# Main_Board.net
KiCad netlist of a schematic drawn in EAGLE
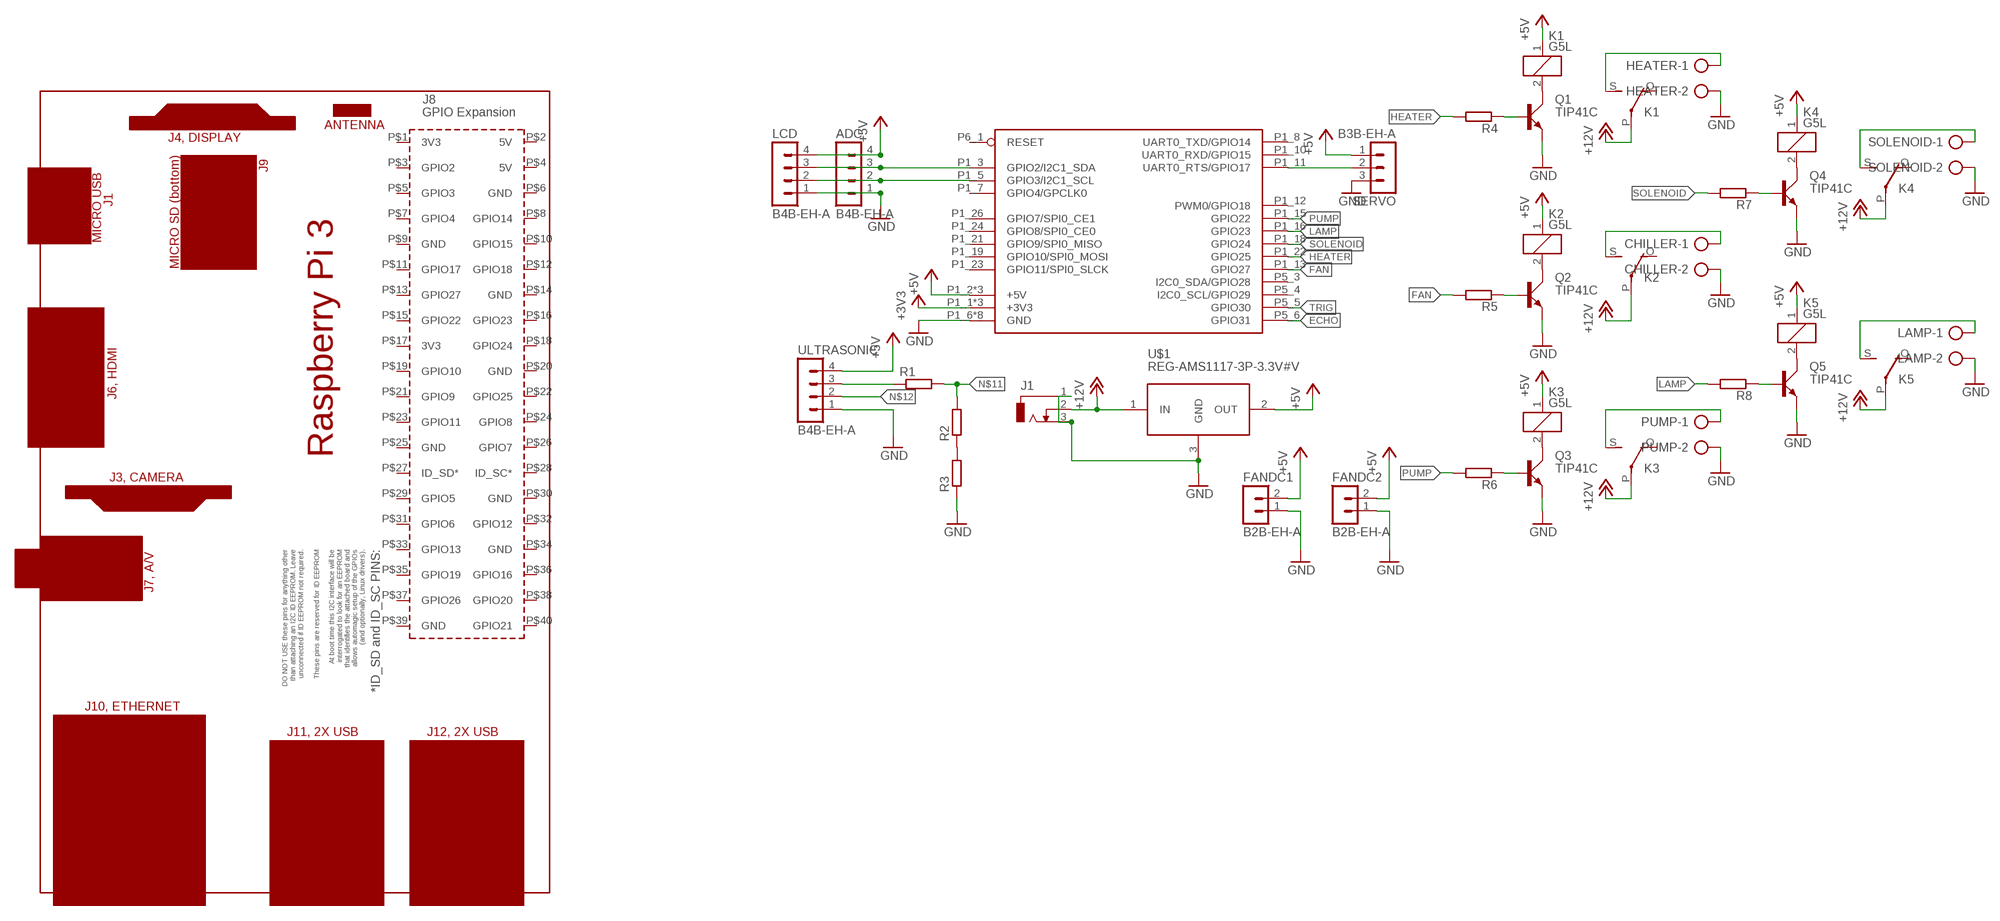
[diagram p0: schematic, sheet 1]

(export (version "E")
  (design (tool "Eeschema 10.0.6"))
  (components
    (comp (ref "ADC")
      (value "B4B-EH-A")
      (footprint "eagle-import:B4B-EH-A")
      (libsource (lib "eagle-import") (part "B4B-EH-A"))
    )
    (comp (ref "CHILLER")
      (value "AK500/2-H")
      (footprint "eagle-import:AK500_2-H")
      (libsource (lib "eagle-import") (part "AK500/2-H"))
    )
    (comp (ref "FANDC1")
      (value "B2B-EH-A")
      (footprint "eagle-import:B2B-EH-A")
      (libsource (lib "eagle-import") (part "B2B-EH-A"))
    )
    (comp (ref "FANDC2")
      (value "B2B-EH-A")
      (footprint "eagle-import:B2B-EH-A")
      (libsource (lib "eagle-import") (part "B2B-EH-A"))
    )
    (comp (ref "HEATER")
      (value "AK500/2-H")
      (footprint "eagle-import:AK500_2-H")
      (libsource (lib "eagle-import") (part "AK500/2-H"))
    )
    (comp (ref "J1")
      (value "DCJ0303")
      (footprint "eagle-import:DCJ0303")
      (libsource (lib "eagle-import") (part "DCJ0303"))
    )
    (comp (ref "K1")
      (value "G5L")
      (footprint "eagle-import:G5LE")
      (libsource (lib "eagle-import") (part "G5L"))
    )
    (comp (ref "K2")
      (value "G5L")
      (footprint "eagle-import:G5LE")
      (libsource (lib "eagle-import") (part "G5L"))
    )
    (comp (ref "K3")
      (value "G5L")
      (footprint "eagle-import:G5LE")
      (libsource (lib "eagle-import") (part "G5L"))
    )
    (comp (ref "K4")
      (value "G5L")
      (footprint "eagle-import:G5LE")
      (libsource (lib "eagle-import") (part "G5L"))
    )
    (comp (ref "K5")
      (value "G5L")
      (footprint "eagle-import:G5LE")
      (libsource (lib "eagle-import") (part "G5L"))
    )
    (comp (ref "LAMP")
      (value "AK500/2-H")
      (footprint "eagle-import:AK500_2-H")
      (libsource (lib "eagle-import") (part "AK500/2-H"))
    )
    (comp (ref "LCD")
      (value "B4B-EH-A")
      (footprint "eagle-import:B4B-EH-A")
      (libsource (lib "eagle-import") (part "B4B-EH-A"))
    )
    (comp (ref "PCB1")
      (value "RPI3")
      (footprint "eagle-import:RPI3")
      (libsource (lib "eagle-import") (part "RPI3"))
    )
    (comp (ref "PUMP")
      (value "AK500/2-H")
      (footprint "eagle-import:AK500_2-H")
      (libsource (lib "eagle-import") (part "AK500/2-H"))
    )
    (comp (ref "Q1")
      (value "TIP41C")
      (footprint "eagle-import:TO220AV")
      (libsource (lib "eagle-import") (part "TIP41C"))
    )
    (comp (ref "Q2")
      (value "TIP41C")
      (footprint "eagle-import:TO220AV")
      (libsource (lib "eagle-import") (part "TIP41C"))
    )
    (comp (ref "Q3")
      (value "TIP41C")
      (footprint "eagle-import:TO220AV")
      (libsource (lib "eagle-import") (part "TIP41C"))
    )
    (comp (ref "Q4")
      (value "TIP41C")
      (footprint "eagle-import:TO220AV")
      (libsource (lib "eagle-import") (part "TIP41C"))
    )
    (comp (ref "Q5")
      (value "TIP41C")
      (footprint "eagle-import:TO220AV")
      (libsource (lib "eagle-import") (part "TIP41C"))
    )
    (comp (ref "R1")
      (value "R-EU_0207/15")
      (footprint "eagle-import:0207_15")
      (libsource (lib "eagle-import") (part "R-EU_0207/15"))
    )
    (comp (ref "R2")
      (value "R-EU_0207/15")
      (footprint "eagle-import:0207_15")
      (libsource (lib "eagle-import") (part "R-EU_0207/15"))
    )
    (comp (ref "R3")
      (value "R-EU_0207/15")
      (footprint "eagle-import:0207_15")
      (libsource (lib "eagle-import") (part "R-EU_0207/15"))
    )
    (comp (ref "R4")
      (value "R-EU_0207/15")
      (footprint "eagle-import:0207_15")
      (libsource (lib "eagle-import") (part "R-EU_0207/15"))
    )
    (comp (ref "R5")
      (value "R-EU_0207/15")
      (footprint "eagle-import:0207_15")
      (libsource (lib "eagle-import") (part "R-EU_0207/15"))
    )
    (comp (ref "R6")
      (value "R-EU_0207/15")
      (footprint "eagle-import:0207_15")
      (libsource (lib "eagle-import") (part "R-EU_0207/15"))
    )
    (comp (ref "R7")
      (value "R-EU_0207/15")
      (footprint "eagle-import:0207_15")
      (libsource (lib "eagle-import") (part "R-EU_0207/15"))
    )
    (comp (ref "R8")
      (value "R-EU_0207/15")
      (footprint "eagle-import:0207_15")
      (libsource (lib "eagle-import") (part "R-EU_0207/15"))
    )
    (comp (ref "SERVO")
      (value "B3B-EH-A")
      (footprint "eagle-import:B3B-EH-A")
      (libsource (lib "eagle-import") (part "B3B-EH-A"))
    )
    (comp (ref "SOLENOID")
      (value "AK500/2-H")
      (footprint "eagle-import:AK500_2-H")
      (libsource (lib "eagle-import") (part "AK500/2-H"))
    )
    (comp (ref "U$1")
      (value "REG-AMS1117-3P-3.3V#V")
      (footprint "eagle-import:REG-AMS1117-3P#V")
      (libsource (lib "eagle-import") (part "REG-AMS1117-3P-#V3.3V"))
    )
    (comp (ref "U$3")
      (value "RPI-B-V2NO_SHIELD")
      (footprint "eagle-import:RPI-B-V2")
      (libsource (lib "eagle-import") (part "RPI-B-V2NO_SHIELD"))
    )
    (comp (ref "ULTRASONIC")
      (value "B4B-EH-A")
      (footprint "eagle-import:B4B-EH-A")
      (libsource (lib "eagle-import") (part "B4B-EH-A"))
    )
  )
  (nets
    (net (code "1") (name "+3V3") (class "Default")
      (node (ref "U$3") (pin "P1_1") (pinfunction "+3V3_P1_1") (pintype "power_in"))
      (node (ref "U$3") (pin "P1_17") (pinfunction "+3V3_P1_17") (pintype "power_in"))
      (node (ref "U$3") (pin "P5_2") (pinfunction "+3V3_P5_2") (pintype "power_in"))
    )
    (net (code "2") (name "+5V") (class "Default")
      (node (ref "ADC") (pin "4") (pinfunction "4_4") (pintype "passive"))
      (node (ref "FANDC1") (pin "2") (pinfunction "2_2") (pintype "passive"))
      (node (ref "FANDC2") (pin "2") (pinfunction "2_2") (pintype "passive"))
      (node (ref "K1") (pin "1") (pinfunction "1_1") (pintype "passive"))
      (node (ref "K2") (pin "1") (pinfunction "1_1") (pintype "passive"))
      (node (ref "K3") (pin "1") (pinfunction "1_1") (pintype "passive"))
      (node (ref "K4") (pin "1") (pinfunction "1_1") (pintype "passive"))
      (node (ref "K5") (pin "1") (pinfunction "1_1") (pintype "passive"))
      (node (ref "LCD") (pin "4") (pinfunction "4_4") (pintype "passive"))
      (node (ref "SERVO") (pin "1") (pinfunction "1_1") (pintype "passive"))
      (node (ref "U$1") (pin "2") (pinfunction "OUT_2") (pintype "bidirectional"))
      (node (ref "U$3") (pin "P1_2") (pinfunction "+5V_P1_2") (pintype "power_in"))
      (node (ref "U$3") (pin "P1_4") (pinfunction "+5V_P1_4") (pintype "power_in"))
      (node (ref "U$3") (pin "P5_1") (pinfunction "+5V_P5_1") (pintype "power_in"))
      (node (ref "ULTRASONIC") (pin "4") (pinfunction "4_4") (pintype "passive"))
    )
    (net (code "3") (name "+12V") (class "Default")
      (node (ref "J1") (pin "2") (pinfunction "2_2") (pintype "passive"))
      (node (ref "K1") (pin "P") (pinfunction "P_P") (pintype "passive"))
      (node (ref "K2") (pin "P") (pinfunction "P_P") (pintype "passive"))
      (node (ref "K3") (pin "P") (pinfunction "P_P") (pintype "passive"))
      (node (ref "K4") (pin "P") (pinfunction "P_P") (pintype "passive"))
      (node (ref "K5") (pin "P") (pinfunction "P_P") (pintype "passive"))
      (node (ref "U$1") (pin "1") (pinfunction "IN_1") (pintype "bidirectional"))
    )
    (net (code "4") (name "/I2C0_SCL{slash}GPIO29") (class "Default")
      (node (ref "U$3") (pin "P5_4") (pinfunction "I2C0_SCL/GPIO29_P5_4") (pintype "power_in"))
    )
    (net (code "5") (name "/I2C0_SDA{slash}GPIO28") (class "Default")
      (node (ref "U$3") (pin "P5_3") (pinfunction "I2C0_SDA/GPIO28_P5_3") (pintype "power_in"))
    )
    (net (code "6") (name "/RESET") (class "Default")
      (node (ref "U$3") (pin "P6_1") (pinfunction "RESET_P6_1") (pintype "power_in"))
    )
    (net (code "7") (name "ECHO") (class "Default")
      (node (ref "U$3") (pin "P5_6") (pinfunction "GPIO31_P5_6") (pintype "power_in"))
    )
    (net (code "8") (name "FAN") (class "Default")
      (node (ref "R5") (pin "2") (pinfunction "2_2") (pintype "passive"))
      (node (ref "U$3") (pin "P1_13") (pinfunction "GPIO27_P1_13") (pintype "bidirectional"))
    )
    (net (code "9") (name "GND") (class "Default")
      (node (ref "ADC") (pin "1") (pinfunction "1_1") (pintype "passive"))
      (node (ref "CHILLER") (pin "2") (pinfunction "KL_2") (pintype "passive"))
      (node (ref "FANDC1") (pin "1") (pinfunction "1_1") (pintype "passive"))
      (node (ref "FANDC2") (pin "1") (pinfunction "1_1") (pintype "passive"))
      (node (ref "HEATER") (pin "2") (pinfunction "KL_2") (pintype "passive"))
      (node (ref "J1") (pin "1") (pinfunction "1_1") (pintype "passive"))
      (node (ref "J1") (pin "3") (pinfunction "3_3") (pintype "passive"))
      (node (ref "LAMP") (pin "2") (pinfunction "KL_2") (pintype "passive"))
      (node (ref "LCD") (pin "1") (pinfunction "1_1") (pintype "passive"))
      (node (ref "PUMP") (pin "2") (pinfunction "KL_2") (pintype "passive"))
      (node (ref "Q1") (pin "E") (pinfunction "E_E") (pintype "passive"))
      (node (ref "Q2") (pin "E") (pinfunction "E_E") (pintype "passive"))
      (node (ref "Q3") (pin "E") (pinfunction "E_E") (pintype "passive"))
      (node (ref "Q4") (pin "E") (pinfunction "E_E") (pintype "passive"))
      (node (ref "Q5") (pin "E") (pinfunction "E_E") (pintype "passive"))
      (node (ref "R3") (pin "1") (pinfunction "1_1") (pintype "passive"))
      (node (ref "SERVO") (pin "3") (pinfunction "3_3") (pintype "passive"))
      (node (ref "SOLENOID") (pin "2") (pinfunction "KL_2") (pintype "passive"))
      (node (ref "U$1") (pin "3") (pinfunction "GND_3") (pintype "bidirectional"))
      (node (ref "U$3") (pin "P1_14") (pinfunction "GND_P1_14") (pintype "power_in"))
      (node (ref "U$3") (pin "P1_20") (pinfunction "GND_P1_20") (pintype "power_in"))
      (node (ref "U$3") (pin "P1_25") (pinfunction "GND_P1_25") (pintype "power_in"))
      (node (ref "U$3") (pin "P1_6") (pinfunction "GND_P1_6") (pintype "power_in"))
      (node (ref "U$3") (pin "P1_9") (pinfunction "GND_P1_9") (pintype "power_in"))
      (node (ref "U$3") (pin "P5_7") (pinfunction "GND_P5_7") (pintype "power_in"))
      (node (ref "U$3") (pin "P5_8") (pinfunction "GND_P5_8") (pintype "power_in"))
      (node (ref "U$3") (pin "P6_2") (pinfunction "GND_P6_2") (pintype "power_in"))
      (node (ref "ULTRASONIC") (pin "1") (pinfunction "1_1") (pintype "passive"))
    )
    (net (code "10") (name "HEATER") (class "Default")
      (node (ref "R4") (pin "2") (pinfunction "2_2") (pintype "passive"))
      (node (ref "U$3") (pin "P1_22") (pinfunction "GPIO25_P1_22") (pintype "bidirectional"))
    )
    (net (code "11") (name "LAMP") (class "Default")
      (node (ref "R8") (pin "2") (pinfunction "2_2") (pintype "passive"))
      (node (ref "U$3") (pin "P1_16") (pinfunction "GPIO23_P1_16") (pintype "bidirectional"))
    )
    (net (code "12") (name "N$11") (class "Default")
      (node (ref "R1") (pin "2") (pinfunction "2_2") (pintype "passive"))
      (node (ref "R2") (pin "2") (pinfunction "2_2") (pintype "passive"))
    )
    (net (code "13") (name "N$12") (class "Default")
      (node (ref "ULTRASONIC") (pin "2") (pinfunction "2_2") (pintype "passive"))
    )
    (net (code "14") (name "Net-(CHILLERA-KL)") (class "Default")
      (node (ref "CHILLER") (pin "1") (pinfunction "KL_1") (pintype "passive"))
      (node (ref "K2") (pin "S") (pinfunction "S_S") (pintype "passive"))
    )
    (net (code "15") (name "Net-(HEATERA-KL)") (class "Default")
      (node (ref "HEATER") (pin "1") (pinfunction "KL_1") (pintype "passive"))
      (node (ref "K1") (pin "S") (pinfunction "S_S") (pintype "passive"))
    )
    (net (code "16") (name "Net-(K1-Pad2)") (class "Default")
      (node (ref "K1") (pin "2") (pinfunction "2_2") (pintype "passive"))
      (node (ref "Q1") (pin "C") (pinfunction "C_C") (pintype "passive"))
    )
    (net (code "17") (name "Net-(K2-Pad2)") (class "Default")
      (node (ref "K2") (pin "2") (pinfunction "2_2") (pintype "passive"))
      (node (ref "Q2") (pin "C") (pinfunction "C_C") (pintype "passive"))
    )
    (net (code "18") (name "Net-(K3-Pad2)") (class "Default")
      (node (ref "K3") (pin "2") (pinfunction "2_2") (pintype "passive"))
      (node (ref "Q3") (pin "C") (pinfunction "C_C") (pintype "passive"))
    )
    (net (code "19") (name "Net-(K4-Pad2)") (class "Default")
      (node (ref "K4") (pin "2") (pinfunction "2_2") (pintype "passive"))
      (node (ref "Q4") (pin "C") (pinfunction "C_C") (pintype "passive"))
    )
    (net (code "20") (name "Net-(K5-Pad2)") (class "Default")
      (node (ref "K5") (pin "2") (pinfunction "2_2") (pintype "passive"))
      (node (ref "Q5") (pin "C") (pinfunction "C_C") (pintype "passive"))
    )
    (net (code "21") (name "Net-(LAMPA-KL)") (class "Default")
      (node (ref "K5") (pin "S") (pinfunction "S_S") (pintype "passive"))
      (node (ref "LAMP") (pin "1") (pinfunction "KL_1") (pintype "passive"))
    )
    (net (code "22") (name "Net-(PUMPA-KL)") (class "Default")
      (node (ref "K3") (pin "S") (pinfunction "S_S") (pintype "passive"))
      (node (ref "PUMP") (pin "1") (pinfunction "KL_1") (pintype "passive"))
    )
    (net (code "23") (name "Net-(Q1-PadB)") (class "Default")
      (node (ref "Q1") (pin "B") (pinfunction "B_B") (pintype "passive"))
      (node (ref "R4") (pin "1") (pinfunction "1_1") (pintype "passive"))
    )
    (net (code "24") (name "Net-(Q2-PadB)") (class "Default")
      (node (ref "Q2") (pin "B") (pinfunction "B_B") (pintype "passive"))
      (node (ref "R5") (pin "1") (pinfunction "1_1") (pintype "passive"))
    )
    (net (code "25") (name "Net-(Q3-PadB)") (class "Default")
      (node (ref "Q3") (pin "B") (pinfunction "B_B") (pintype "passive"))
      (node (ref "R6") (pin "1") (pinfunction "1_1") (pintype "passive"))
    )
    (net (code "26") (name "Net-(Q4-PadB)") (class "Default")
      (node (ref "Q4") (pin "B") (pinfunction "B_B") (pintype "passive"))
      (node (ref "R7") (pin "1") (pinfunction "1_1") (pintype "passive"))
    )
    (net (code "27") (name "Net-(Q5-PadB)") (class "Default")
      (node (ref "Q5") (pin "B") (pinfunction "B_B") (pintype "passive"))
      (node (ref "R8") (pin "1") (pinfunction "1_1") (pintype "passive"))
    )
    (net (code "28") (name "Net-(R1-Pad1)") (class "Default")
      (node (ref "R1") (pin "1") (pinfunction "1_1") (pintype "passive"))
      (node (ref "ULTRASONIC") (pin "3") (pinfunction "3_3") (pintype "passive"))
    )
    (net (code "29") (name "Net-(R2-Pad1)") (class "Default")
      (node (ref "R2") (pin "1") (pinfunction "1_1") (pintype "passive"))
      (node (ref "R3") (pin "2") (pinfunction "2_2") (pintype "passive"))
    )
    (net (code "30") (name "Net-(SOLENOIDA-KL)") (class "Default")
      (node (ref "K4") (pin "S") (pinfunction "S_S") (pintype "passive"))
      (node (ref "SOLENOID") (pin "1") (pinfunction "KL_1") (pintype "passive"))
    )
    (net (code "31") (name "Net-(U$3-GPIO2{slash}I2C1_SDA)") (class "Default")
      (node (ref "ADC") (pin "3") (pinfunction "3_3") (pintype "passive"))
      (node (ref "LCD") (pin "3") (pinfunction "3_3") (pintype "passive"))
      (node (ref "U$3") (pin "P1_3") (pinfunction "GPIO2/I2C1_SDA_P1_3") (pintype "bidirectional"))
    )
    (net (code "32") (name "Net-(U$3-GPIO3{slash}I2C1_SCL)") (class "Default")
      (node (ref "ADC") (pin "2") (pinfunction "2_2") (pintype "passive"))
      (node (ref "LCD") (pin "2") (pinfunction "2_2") (pintype "passive"))
      (node (ref "U$3") (pin "P1_5") (pinfunction "GPIO3/I2C1_SCL_P1_5") (pintype "bidirectional"))
    )
    (net (code "33") (name "Net-(U$3-UART0_RTS{slash}GPIO17)") (class "Default")
      (node (ref "SERVO") (pin "2") (pinfunction "2_2") (pintype "passive"))
      (node (ref "U$3") (pin "P1_11") (pinfunction "UART0_RTS/GPIO17_P1_11") (pintype "bidirectional"))
    )
    (net (code "34") (name "PUMP") (class "Default")
      (node (ref "R6") (pin "2") (pinfunction "2_2") (pintype "passive"))
      (node (ref "U$3") (pin "P1_15") (pinfunction "GPIO22_P1_15") (pintype "bidirectional"))
    )
    (net (code "35") (name "SOLENOID") (class "Default")
      (node (ref "R7") (pin "2") (pinfunction "2_2") (pintype "passive"))
      (node (ref "U$3") (pin "P1_18") (pinfunction "GPIO24_P1_18") (pintype "bidirectional"))
    )
    (net (code "36") (name "TRIG") (class "Default")
      (node (ref "U$3") (pin "P5_5") (pinfunction "GPIO30_P5_5") (pintype "power_in"))
    )
    (net (code "37") (name "unconnected-(K1-PadO)") (class "Default")
      (node (ref "K1") (pin "O") (pinfunction "O_O") (pintype "passive"))
    )
    (net (code "38") (name "unconnected-(K2-PadO)") (class "Default")
      (node (ref "K2") (pin "O") (pinfunction "O_O") (pintype "passive"))
    )
    (net (code "39") (name "unconnected-(K3-PadO)") (class "Default")
      (node (ref "K3") (pin "O") (pinfunction "O_O") (pintype "passive"))
    )
    (net (code "40") (name "unconnected-(K4-PadO)") (class "Default")
      (node (ref "K4") (pin "O") (pinfunction "O_O") (pintype "passive"))
    )
    (net (code "41") (name "unconnected-(K5-PadO)") (class "Default")
      (node (ref "K5") (pin "O") (pinfunction "O_O") (pintype "passive"))
    )
    (net (code "42") (name "unconnected-(PCB1-3V3-PadP$1)") (class "Default")
      (node (ref "PCB1") (pin "P$1") (pinfunction "3V3_P$1") (pintype "bidirectional"))
    )
    (net (code "43") (name "unconnected-(PCB1-3V3-PadP$17)") (class "Default")
      (node (ref "PCB1") (pin "P$17") (pinfunction "3V3_P$17") (pintype "bidirectional"))
    )
    (net (code "44") (name "unconnected-(PCB1-5V-PadP$2)") (class "Default")
      (node (ref "PCB1") (pin "P$2") (pinfunction "5V_P$2") (pintype "bidirectional"))
    )
    (net (code "45") (name "unconnected-(PCB1-5V-PadP$4)") (class "Default")
      (node (ref "PCB1") (pin "P$4") (pinfunction "5V_P$4") (pintype "bidirectional"))
    )
    (net (code "46") (name "unconnected-(PCB1-GND-PadP$6)") (class "Default")
      (node (ref "PCB1") (pin "P$6") (pinfunction "GND_P$6") (pintype "bidirectional"))
    )
    (net (code "47") (name "unconnected-(PCB1-GND-PadP$9)") (class "Default")
      (node (ref "PCB1") (pin "P$9") (pinfunction "GND_P$9") (pintype "bidirectional"))
    )
    (net (code "48") (name "unconnected-(PCB1-GND-PadP$14)") (class "Default")
      (node (ref "PCB1") (pin "P$14") (pinfunction "GND_P$14") (pintype "bidirectional"))
    )
    (net (code "49") (name "unconnected-(PCB1-GND-PadP$20)") (class "Default")
      (node (ref "PCB1") (pin "P$20") (pinfunction "GND_P$20") (pintype "bidirectional"))
    )
    (net (code "50") (name "unconnected-(PCB1-GND-PadP$25)") (class "Default")
      (node (ref "PCB1") (pin "P$25") (pinfunction "GND_P$25") (pintype "bidirectional"))
    )
    (net (code "51") (name "unconnected-(PCB1-GND-PadP$30)") (class "Default")
      (node (ref "PCB1") (pin "P$30") (pinfunction "GND_P$30") (pintype "bidirectional"))
    )
    (net (code "52") (name "unconnected-(PCB1-GND-PadP$34)") (class "Default")
      (node (ref "PCB1") (pin "P$34") (pinfunction "GND_P$34") (pintype "bidirectional"))
    )
    (net (code "53") (name "unconnected-(PCB1-GND-PadP$39)") (class "Default")
      (node (ref "PCB1") (pin "P$39") (pinfunction "GND_P$39") (pintype "bidirectional"))
    )
    (net (code "54") (name "unconnected-(PCB1-GPIO2-PadP$3)") (class "Default")
      (node (ref "PCB1") (pin "P$3") (pinfunction "GPIO2_P$3") (pintype "bidirectional"))
    )
    (net (code "55") (name "unconnected-(PCB1-GPIO3-PadP$5)") (class "Default")
      (node (ref "PCB1") (pin "P$5") (pinfunction "GPIO3_P$5") (pintype "bidirectional"))
    )
    (net (code "56") (name "unconnected-(PCB1-GPIO4-PadP$7)") (class "Default")
      (node (ref "PCB1") (pin "P$7") (pinfunction "GPIO4_P$7") (pintype "bidirectional"))
    )
    (net (code "57") (name "unconnected-(PCB1-GPIO5-PadP$29)") (class "Default")
      (node (ref "PCB1") (pin "P$29") (pinfunction "GPIO5_P$29") (pintype "bidirectional"))
    )
    (net (code "58") (name "unconnected-(PCB1-GPIO6-PadP$31)") (class "Default")
      (node (ref "PCB1") (pin "P$31") (pinfunction "GPIO6_P$31") (pintype "bidirectional"))
    )
    (net (code "59") (name "unconnected-(PCB1-GPIO7-PadP$26)") (class "Default")
      (node (ref "PCB1") (pin "P$26") (pinfunction "GPIO7_P$26") (pintype "bidirectional"))
    )
    (net (code "60") (name "unconnected-(PCB1-GPIO8-PadP$24)") (class "Default")
      (node (ref "PCB1") (pin "P$24") (pinfunction "GPIO8_P$24") (pintype "bidirectional"))
    )
    (net (code "61") (name "unconnected-(PCB1-GPIO9-PadP$21)") (class "Default")
      (node (ref "PCB1") (pin "P$21") (pinfunction "GPIO9_P$21") (pintype "bidirectional"))
    )
    (net (code "62") (name "unconnected-(PCB1-GPIO10-PadP$19)") (class "Default")
      (node (ref "PCB1") (pin "P$19") (pinfunction "GPIO10_P$19") (pintype "bidirectional"))
    )
    (net (code "63") (name "unconnected-(PCB1-GPIO11-PadP$23)") (class "Default")
      (node (ref "PCB1") (pin "P$23") (pinfunction "GPIO11_P$23") (pintype "bidirectional"))
    )
    (net (code "64") (name "unconnected-(PCB1-GPIO12-PadP$32)") (class "Default")
      (node (ref "PCB1") (pin "P$32") (pinfunction "GPIO12_P$32") (pintype "bidirectional"))
    )
    (net (code "65") (name "unconnected-(PCB1-GPIO13-PadP$33)") (class "Default")
      (node (ref "PCB1") (pin "P$33") (pinfunction "GPIO13_P$33") (pintype "bidirectional"))
    )
    (net (code "66") (name "unconnected-(PCB1-GPIO14-PadP$8)") (class "Default")
      (node (ref "PCB1") (pin "P$8") (pinfunction "GPIO14_P$8") (pintype "bidirectional"))
    )
    (net (code "67") (name "unconnected-(PCB1-GPIO15-PadP$10)") (class "Default")
      (node (ref "PCB1") (pin "P$10") (pinfunction "GPIO15_P$10") (pintype "bidirectional"))
    )
    (net (code "68") (name "unconnected-(PCB1-GPIO16-PadP$36)") (class "Default")
      (node (ref "PCB1") (pin "P$36") (pinfunction "GPIO16_P$36") (pintype "bidirectional"))
    )
    (net (code "69") (name "unconnected-(PCB1-GPIO17-PadP$11)") (class "Default")
      (node (ref "PCB1") (pin "P$11") (pinfunction "GPIO17_P$11") (pintype "bidirectional"))
    )
    (net (code "70") (name "unconnected-(PCB1-GPIO18-PadP$12)") (class "Default")
      (node (ref "PCB1") (pin "P$12") (pinfunction "GPIO18_P$12") (pintype "bidirectional"))
    )
    (net (code "71") (name "unconnected-(PCB1-GPIO19-PadP$35)") (class "Default")
      (node (ref "PCB1") (pin "P$35") (pinfunction "GPIO19_P$35") (pintype "bidirectional"))
    )
    (net (code "72") (name "unconnected-(PCB1-GPIO20-PadP$38)") (class "Default")
      (node (ref "PCB1") (pin "P$38") (pinfunction "GPIO20_P$38") (pintype "bidirectional"))
    )
    (net (code "73") (name "unconnected-(PCB1-GPIO21-PadP$40)") (class "Default")
      (node (ref "PCB1") (pin "P$40") (pinfunction "GPIO21_P$40") (pintype "bidirectional"))
    )
    (net (code "74") (name "unconnected-(PCB1-GPIO22-PadP$15)") (class "Default")
      (node (ref "PCB1") (pin "P$15") (pinfunction "GPIO22_P$15") (pintype "bidirectional"))
    )
    (net (code "75") (name "unconnected-(PCB1-GPIO23-PadP$16)") (class "Default")
      (node (ref "PCB1") (pin "P$16") (pinfunction "GPIO23_P$16") (pintype "bidirectional"))
    )
    (net (code "76") (name "unconnected-(PCB1-GPIO24-PadP$18)") (class "Default")
      (node (ref "PCB1") (pin "P$18") (pinfunction "GPIO24_P$18") (pintype "bidirectional"))
    )
    (net (code "77") (name "unconnected-(PCB1-GPIO25-PadP$22)") (class "Default")
      (node (ref "PCB1") (pin "P$22") (pinfunction "GPIO25_P$22") (pintype "bidirectional"))
    )
    (net (code "78") (name "unconnected-(PCB1-GPIO26-PadP$37)") (class "Default")
      (node (ref "PCB1") (pin "P$37") (pinfunction "GPIO26_P$37") (pintype "bidirectional"))
    )
    (net (code "79") (name "unconnected-(PCB1-GPIO27-PadP$13)") (class "Default")
      (node (ref "PCB1") (pin "P$13") (pinfunction "GPIO27_P$13") (pintype "bidirectional"))
    )
    (net (code "80") (name "unconnected-(PCB1-ID_SC*-PadP$28)") (class "Default")
      (node (ref "PCB1") (pin "P$28") (pinfunction "ID_SC*_P$28") (pintype "bidirectional"))
    )
    (net (code "81") (name "unconnected-(PCB1-ID_SD*-PadP$27)") (class "Default")
      (node (ref "PCB1") (pin "P$27") (pinfunction "ID_SD*_P$27") (pintype "bidirectional"))
    )
    (net (code "82") (name "unconnected-(U$3-GPIO4{slash}GPCLK0-PadP1_7)") (class "Default")
      (node (ref "U$3") (pin "P1_7") (pinfunction "GPIO4/GPCLK0_P1_7") (pintype "bidirectional"))
    )
    (net (code "83") (name "unconnected-(U$3-GPIO7{slash}SPI0_CE1-PadP1_26)") (class "Default")
      (node (ref "U$3") (pin "P1_26") (pinfunction "GPIO7/SPI0_CE1_P1_26") (pintype "bidirectional"))
    )
    (net (code "84") (name "unconnected-(U$3-GPIO8{slash}SPI0_CE0-PadP1_24)") (class "Default")
      (node (ref "U$3") (pin "P1_24") (pinfunction "GPIO8/SPI0_CE0_P1_24") (pintype "bidirectional"))
    )
    (net (code "85") (name "unconnected-(U$3-GPIO9{slash}SPI0_MISO-PadP1_21)") (class "Default")
      (node (ref "U$3") (pin "P1_21") (pinfunction "GPIO9/SPI0_MISO_P1_21") (pintype "bidirectional"))
    )
    (net (code "86") (name "unconnected-(U$3-GPIO10{slash}SPI0_MOSI-PadP1_19)") (class "Default")
      (node (ref "U$3") (pin "P1_19") (pinfunction "GPIO10/SPI0_MOSI_P1_19") (pintype "bidirectional"))
    )
    (net (code "87") (name "unconnected-(U$3-GPIO11{slash}SPI0_SLCK-PadP1_23)") (class "Default")
      (node (ref "U$3") (pin "P1_23") (pinfunction "GPIO11/SPI0_SLCK_P1_23") (pintype "bidirectional"))
    )
    (net (code "88") (name "unconnected-(U$3-PWM0{slash}GPIO18-PadP1_12)") (class "Default")
      (node (ref "U$3") (pin "P1_12") (pinfunction "PWM0/GPIO18_P1_12") (pintype "bidirectional"))
    )
    (net (code "89") (name "unconnected-(U$3-UART0_RXD{slash}GPIO15-PadP1_10)") (class "Default")
      (node (ref "U$3") (pin "P1_10") (pinfunction "UART0_RXD/GPIO15_P1_10") (pintype "bidirectional"))
    )
    (net (code "90") (name "unconnected-(U$3-UART0_TXD{slash}GPIO14-PadP1_8)") (class "Default")
      (node (ref "U$3") (pin "P1_8") (pinfunction "UART0_TXD/GPIO14_P1_8") (pintype "bidirectional"))
    )
  )
)
